# PowerSheet.net
KiCad netlist of a schematic drawn in Altium Designer
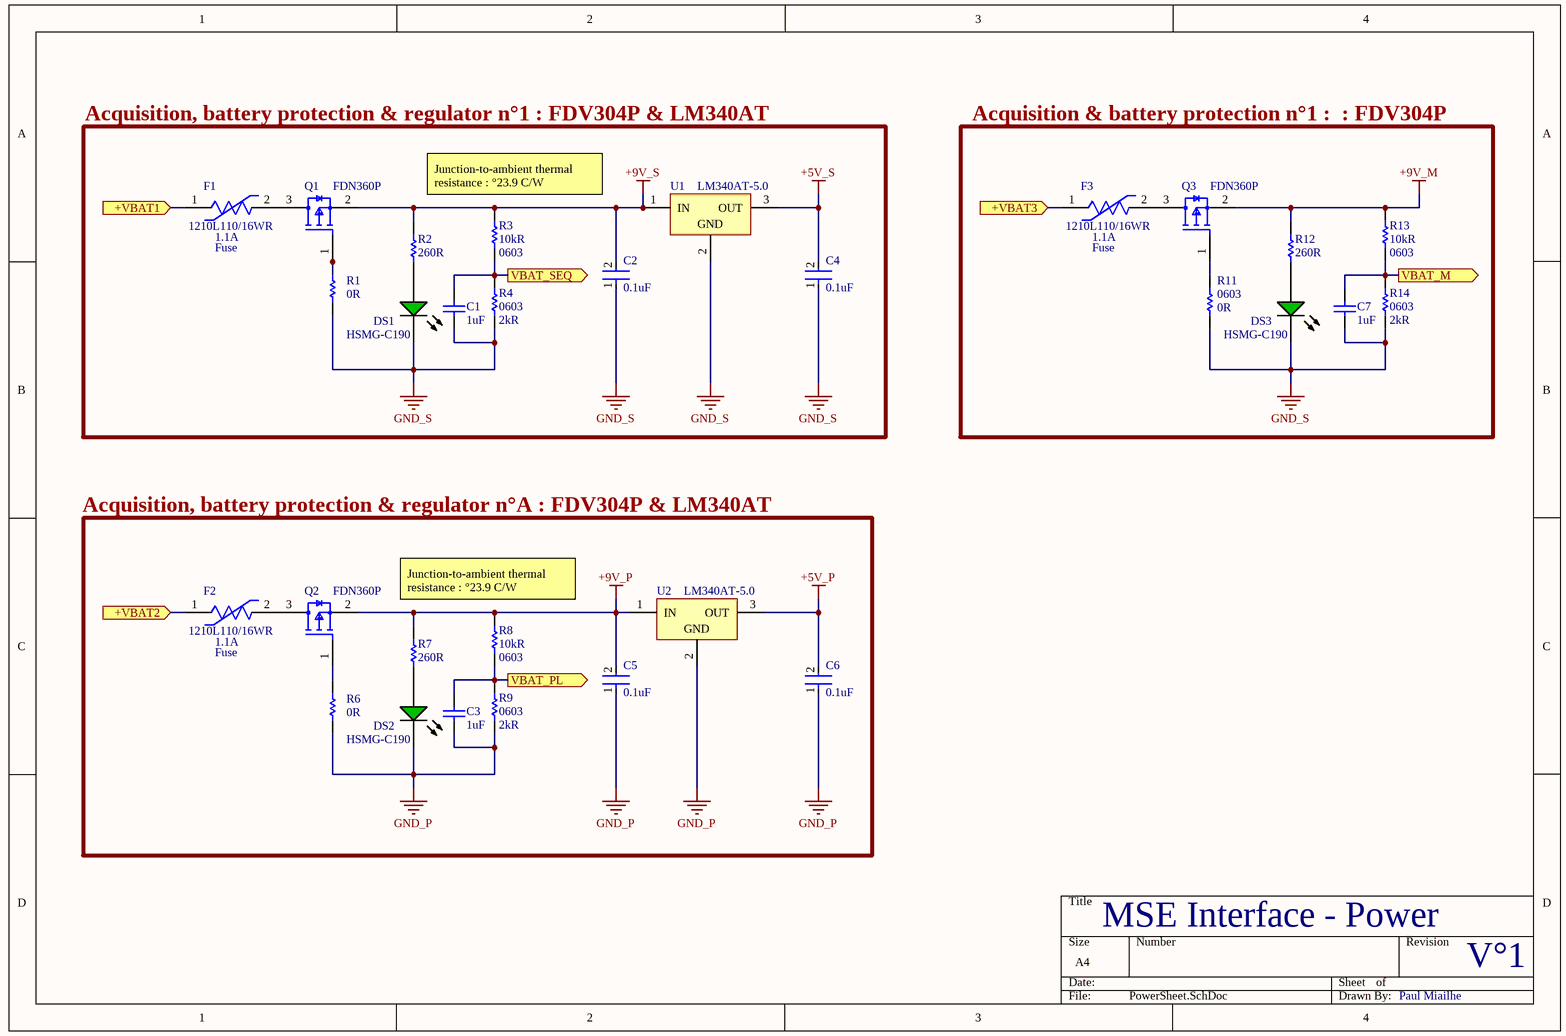
[diagram p0: PowerSheet.SchDoc]

(export (version "E")
  (design (tool "Eeschema 10.0.6"))
  (components
    (comp (ref "C1")
      (value "GRM188R61E105KA12D")
      (footprint "CAPC1608X90X35LL10T15")
      (fields
        (field (name "MANUFACTURER") "Murata")
        (field (name "CAPACITANCE") "1uF")
        (field (name "TOLERANCE") "10%")
        (field (name "VOLTAGE") "25V")
      )
      (libsource (lib "Altium Content Vault") (part "CAP"))
    )
    (comp (ref "C2")
      (value "0.1uF")
      (footprint "FP-RCE1K1-2_5-MFG")
      (description "Cap Ceramic Monolithic 220nF 50V 10% Thru-Hole Bulk")
      (fields (field (name "TOLERANCE") "10%"))
      (libsource (lib "Altium Content Vault") (part "02cd4be3c70576c341d710602a673aa"))
    )
    (comp (ref "C3")
      (value "GRM188R61E105KA12D")
      (footprint "CAPC1608X90X35LL10T15")
      (fields
        (field (name "MANUFACTURER") "Murata")
        (field (name "CAPACITANCE") "1uF")
        (field (name "TOLERANCE") "10%")
        (field (name "VOLTAGE") "25V")
      )
      (libsource (lib "Altium Content Vault") (part "CAP"))
    )
    (comp (ref "C4")
      (value "0.1uF")
      (footprint "FP-RCE1K1-2_5-MFG")
      (description "Cap Ceramic Monolithic 220nF 50V 10% Thru-Hole Bulk")
      (fields (field (name "TOLERANCE") "10%"))
      (libsource (lib "Altium Content Vault") (part "02cd4be3c70576c341d710602a673aa"))
    )
    (comp (ref "C5")
      (value "0.1uF")
      (footprint "FP-RCE1K1-2_5-MFG")
      (description "Cap Ceramic Monolithic 220nF 50V 10% Thru-Hole Bulk")
      (fields (field (name "TOLERANCE") "10%"))
      (libsource (lib "Altium Content Vault") (part "02cd4be3c70576c341d710602a673aa"))
    )
    (comp (ref "C6")
      (value "0.1uF")
      (footprint "FP-RCE1K1-2_5-MFG")
      (description "Cap Ceramic Monolithic 220nF 50V 10% Thru-Hole Bulk")
      (fields (field (name "TOLERANCE") "10%"))
      (libsource (lib "Altium Content Vault") (part "02cd4be3c70576c341d710602a673aa"))
    )
    (comp (ref "C7")
      (value "GRM188R61E105KA12D")
      (footprint "CAPC1608X90X35LL10T15")
      (fields
        (field (name "MANUFACTURER") "Murata")
        (field (name "CAPACITANCE") "1uF")
        (field (name "TOLERANCE") "10%")
        (field (name "VOLTAGE") "25V")
      )
      (libsource (lib "Altium Content Vault") (part "CAP"))
    )
    (comp (ref "DS1")
      (value "HSMG-C190")
      (footprint "AVAG-HSMX-C190_V")
      (description "Chip LED, Green, 2.2 V, -40 to 85 degC, 2-Pin SMD, RoHS, Tape and Reel")
      (libsource (lib "Altium Content Vault") (part "LED-GREEN-AK-2"))
    )
    (comp (ref "DS2")
      (value "HSMG-C190")
      (footprint "AVAG-HSMX-C190_V")
      (description "Chip LED, Green, 2.2 V, -40 to 85 degC, 2-Pin SMD, RoHS, Tape and Reel")
      (libsource (lib "Altium Content Vault") (part "LED-GREEN-AK-2"))
    )
    (comp (ref "DS3")
      (value "HSMG-C190")
      (footprint "AVAG-HSMX-C190_V")
      (description "Chip LED, Green, 2.2 V, -40 to 85 degC, 2-Pin SMD, RoHS, Tape and Reel")
      (libsource (lib "Altium Content Vault") (part "LED-GREEN-AK-2"))
    )
    (comp (ref "F1")
      (value "1210L110/16WR")
      (footprint "FP-1210L110-16WR-MFG")
      (description "PTC RESET FUSE 16V 1.1A 1210")
      (fields
        (field (name "HOLD CURRENT") "1.1A")
        (field (name "CATEGORY") "Fuse")
        (field (name "OCTOPART") "https://octopart.com/1210l110%2F16wr-littelfuse-28867107")
        (field (name "MANUFACTURER") "Littelfuse Inc")
      )
      (libsource (lib "Altium Content Vault") (part "1c6d77a0208143737455a0c7eb396be"))
    )
    (comp (ref "F2")
      (value "1210L110/16WR")
      (footprint "FP-1210L110-16WR-MFG")
      (description "PTC RESET FUSE 16V 1.1A 1210")
      (fields
        (field (name "HOLD CURRENT") "1.1A")
        (field (name "CATEGORY") "Fuse")
        (field (name "OCTOPART") "https://octopart.com/1210l110%2F16wr-littelfuse-28867107")
        (field (name "MANUFACTURER") "Littelfuse Inc")
      )
      (libsource (lib "Altium Content Vault") (part "1c6d77a0208143737455a0c7eb396be"))
    )
    (comp (ref "F3")
      (value "1210L110/16WR")
      (footprint "FP-1210L110-16WR-MFG")
      (description "PTC RESET FUSE 16V 1.1A 1210")
      (fields
        (field (name "HOLD CURRENT") "1.1A")
        (field (name "CATEGORY") "Fuse")
        (field (name "OCTOPART") "https://octopart.com/1210l110%2F16wr-littelfuse-28867107")
        (field (name "MANUFACTURER") "Littelfuse Inc")
      )
      (libsource (lib "Altium Content Vault") (part "1c6d77a0208143737455a0c7eb396be"))
    )
    (comp (ref "Q1")
      (value "FDN360P")
      (footprint "FP-527AG-IPC_B")
      (description "MOSFET P-CH 30V 2A SSOT3")
      (libsource (lib "Altium Content Vault") (part "d96140c8e79ef71348df71fb49a9466"))
    )
    (comp (ref "Q2")
      (value "FDN360P")
      (footprint "FP-527AG-IPC_B")
      (description "MOSFET P-CH 30V 2A SSOT3")
      (libsource (lib "Altium Content Vault") (part "d96140c8e79ef71348df71fb49a9466"))
    )
    (comp (ref "Q3")
      (value "FDN360P")
      (footprint "FP-527AG-IPC_B")
      (description "MOSFET P-CH 30V 2A SSOT3")
      (libsource (lib "Altium Content Vault") (part "d96140c8e79ef71348df71fb49a9466"))
    )
    (comp (ref "R1")
      (value "RC0603JR-070RL")
      (footprint "RESC1608X55X25ML10T15")
      (description "Chip Resistor, 0 Ohm, +/- 5%, 0.1 W, -55 to 155 degC, 0603 (1608 Metric), RoHS, Tape and Reel")
      (fields
        (field (name "TOLERANCE") "5%")
        (field (name "RESISTANCE") "0R")
        (field (name "MANUFACTURER") "Yageo")
      )
      (libsource (lib "Altium Content Vault") (part "RES-2"))
    )
    (comp (ref "R2")
      (value "260R")
      (footprint "RESC1609X50X30NL8T20")
      (fields (field (name "MANUFACTURER") "Vishay Semiconductor"))
      (libsource (lib "Altium Content Vault") (part "RES-2"))
    )
    (comp (ref "R3")
      (value "ERJ3EKF1002V")
      (footprint "RESC1609X55X30LL15T15")
      (description "Chip Resistor, 10 KOhm, +/- 1%, 0.1 W, -55 to 155 degC, 0603 (1608 Metric), RoHS, Tape and Reel")
      (fields
        (field (name "RESISTANCE") "10kR")
        (field (name "CASE CODE (IMPERIAL)") "0603")
        (field (name "TOLERANCE") "1%")
        (field (name "MANUFACTURER") "Panasonic")
      )
      (libsource (lib "Altium Content Vault") (part "RES-2"))
    )
    (comp (ref "R4")
      (value "ERJ-3EKF2001V")
      (footprint "RESC1608X55X30ML15T15")
      (fields
        (field (name "MANUFACTURER") "Panasonic")
        (field (name "CASE CODE (IMPERIAL)") "0603")
        (field (name "RESISTANCE") "2kR")
        (field (name "TOLERANCE") "1%")
      )
      (libsource (lib "Altium Content Vault") (part "RES"))
    )
    (comp (ref "R6")
      (value "RC0603JR-070RL")
      (footprint "RESC1608X55X25ML10T15")
      (description "Chip Resistor, 0 Ohm, +/- 5%, 0.1 W, -55 to 155 degC, 0603 (1608 Metric), RoHS, Tape and Reel")
      (fields
        (field (name "TOLERANCE") "5%")
        (field (name "RESISTANCE") "0R")
        (field (name "MANUFACTURER") "Yageo")
      )
      (libsource (lib "Altium Content Vault") (part "RES-2"))
    )
    (comp (ref "R7")
      (value "260R")
      (footprint "RESC1609X50X30NL8T20")
      (fields (field (name "MANUFACTURER") "Vishay Semiconductor"))
      (libsource (lib "Altium Content Vault") (part "RES-2"))
    )
    (comp (ref "R8")
      (value "ERJ3EKF1002V")
      (footprint "RESC1609X55X30LL15T15")
      (description "Chip Resistor, 10 KOhm, +/- 1%, 0.1 W, -55 to 155 degC, 0603 (1608 Metric), RoHS, Tape and Reel")
      (fields
        (field (name "RESISTANCE") "10kR")
        (field (name "CASE CODE (IMPERIAL)") "0603")
        (field (name "TOLERANCE") "1%")
        (field (name "MANUFACTURER") "Panasonic")
      )
      (libsource (lib "Altium Content Vault") (part "RES-2"))
    )
    (comp (ref "R9")
      (value "ERJ-3EKF2001V")
      (footprint "RESC1608X55X30ML15T15")
      (fields
        (field (name "MANUFACTURER") "Panasonic")
        (field (name "CASE CODE (IMPERIAL)") "0603")
        (field (name "RESISTANCE") "2kR")
        (field (name "TOLERANCE") "1%")
      )
      (libsource (lib "Altium Content Vault") (part "RES"))
    )
    (comp (ref "R11")
      (value "RC0603JR-070RL")
      (footprint "RESC1608X55X25ML10T15")
      (description "Chip Resistor, 0 Ohm, +/- 5%, 0.1 W, -55 to 155 degC, 0603 (1608 Metric), RoHS, Tape and Reel")
      (fields
        (field (name "TOLERANCE") "5%")
        (field (name "PACKAGE REFERENCE") "0603")
        (field (name "RESISTANCE") "0R")
        (field (name "MANUFACTURER") "Yageo")
      )
      (libsource (lib "Altium Content Vault") (part "RES-2"))
    )
    (comp (ref "R12")
      (value "260R")
      (footprint "RESC1609X50X30NL8T20")
      (fields (field (name "MANUFACTURER") "Vishay Semiconductor"))
      (libsource (lib "Altium Content Vault") (part "RES-2"))
    )
    (comp (ref "R13")
      (value "ERJ3EKF1002V")
      (footprint "RESC1609X55X30LL15T15")
      (description "Chip Resistor, 10 KOhm, +/- 1%, 0.1 W, -55 to 155 degC, 0603 (1608 Metric), RoHS, Tape and Reel")
      (fields
        (field (name "RESISTANCE") "10kR")
        (field (name "CASE CODE (IMPERIAL)") "0603")
        (field (name "TOLERANCE") "1%")
        (field (name "MANUFACTURER") "Panasonic")
      )
      (libsource (lib "Altium Content Vault") (part "RES-2"))
    )
    (comp (ref "R14")
      (value "ERJ-3EKF2001V")
      (footprint "RESC1608X55X30ML15T15")
      (fields
        (field (name "MANUFACTURER") "Panasonic")
        (field (name "CASE CODE (IMPERIAL)") "0603")
        (field (name "RESISTANCE") "2kR")
        (field (name "TOLERANCE") "1%")
      )
      (libsource (lib "Altium Content Vault") (part "RES"))
    )
    (comp (ref "U1")
      (value "LM340AT-5.0")
      (footprint "NDE0003A")
      (description "Series 3-Terminal Positive Regulators, 3-pin TO-220")
      (fields (field (name "MANUFACTURER") "Texas Instruments"))
      (libsource (lib "Altium Content Vault") (part "PM-REG-LM2940-SIL3"))
    )
    (comp (ref "U2")
      (value "LM340AT-5.0")
      (footprint "NDE0003A")
      (description "Series 3-Terminal Positive Regulators, 3-pin TO-220")
      (fields (field (name "MANUFACTURER") "Texas Instruments"))
      (libsource (lib "Altium Content Vault") (part "PM-REG-LM2940-SIL3"))
    )
  )
  (nets
    (net (code "1") (name "+5V_P") (class "Default")
      (node (ref "C6") (pin "2") (pinfunction "2_2") (pintype "passive"))
      (node (ref "U2") (pin "3") (pinfunction "OUT_3") (pintype "power_in"))
    )
    (net (code "2") (name "+5V_S") (class "Default")
      (node (ref "C4") (pin "2") (pinfunction "2_2") (pintype "passive"))
      (node (ref "U1") (pin "3") (pinfunction "OUT_3") (pintype "power_in"))
    )
    (net (code "3") (name "+9V_M") (class "Default")
      (node (ref "Q3") (pin "2") (pinfunction "S_2") (pintype "passive"))
      (node (ref "R12") (pin "1") (pinfunction "1_1") (pintype "passive"))
      (node (ref "R13") (pin "2") (pinfunction "2_2") (pintype "passive"))
    )
    (net (code "4") (name "+9V_P") (class "Default")
      (node (ref "C5") (pin "2") (pinfunction "2_2") (pintype "passive"))
      (node (ref "Q2") (pin "2") (pinfunction "S_2") (pintype "passive"))
      (node (ref "R7") (pin "1") (pinfunction "1_1") (pintype "passive"))
      (node (ref "R8") (pin "2") (pinfunction "2_2") (pintype "passive"))
      (node (ref "U2") (pin "1") (pinfunction "IN_1") (pintype "power_in"))
    )
    (net (code "5") (name "+9V_S") (class "Default")
      (node (ref "C2") (pin "2") (pinfunction "2_2") (pintype "passive"))
      (node (ref "Q1") (pin "2") (pinfunction "S_2") (pintype "passive"))
      (node (ref "R2") (pin "1") (pinfunction "1_1") (pintype "passive"))
      (node (ref "R3") (pin "2") (pinfunction "2_2") (pintype "passive"))
      (node (ref "U1") (pin "1") (pinfunction "IN_1") (pintype "power_in"))
    )
    (net (code "6") (name "/+VBAT1") (class "Default")
      (node (ref "F1") (pin "1") (pinfunction "1_1") (pintype "passive"))
    )
    (net (code "7") (name "/+VBAT2") (class "Default")
      (node (ref "F2") (pin "1") (pinfunction "1_1") (pintype "passive"))
    )
    (net (code "8") (name "/+VBAT3") (class "Default")
      (node (ref "F3") (pin "1") (pinfunction "1_1") (pintype "passive"))
    )
    (net (code "9") (name "/VBAT_M") (class "Default")
      (node (ref "C7") (pin "2") (pinfunction "2_2") (pintype "passive"))
      (node (ref "R13") (pin "1") (pinfunction "1_1") (pintype "passive"))
      (node (ref "R14") (pin "2") (pinfunction "2_2") (pintype "passive"))
    )
    (net (code "10") (name "/VBAT_PL") (class "Default")
      (node (ref "C3") (pin "2") (pinfunction "2_2") (pintype "passive"))
      (node (ref "R8") (pin "1") (pinfunction "1_1") (pintype "passive"))
      (node (ref "R9") (pin "2") (pinfunction "2_2") (pintype "passive"))
    )
    (net (code "11") (name "/VBAT_SEQ") (class "Default")
      (node (ref "C1") (pin "2") (pinfunction "2_2") (pintype "passive"))
      (node (ref "R3") (pin "1") (pinfunction "1_1") (pintype "passive"))
      (node (ref "R4") (pin "2") (pinfunction "2_2") (pintype "passive"))
    )
    (net (code "12") (name "GND_P") (class "Default")
      (node (ref "C3") (pin "1") (pinfunction "1_1") (pintype "passive"))
      (node (ref "C5") (pin "1") (pinfunction "1_1") (pintype "passive"))
      (node (ref "C6") (pin "1") (pinfunction "1_1") (pintype "passive"))
      (node (ref "DS2") (pin "2") (pinfunction "K_2") (pintype "passive"))
      (node (ref "R6") (pin "1") (pinfunction "1_1") (pintype "passive"))
      (node (ref "R9") (pin "1") (pinfunction "1_1") (pintype "passive"))
      (node (ref "U2") (pin "2") (pinfunction "GND_2") (pintype "power_in"))
    )
    (net (code "13") (name "GND_S") (class "Default")
      (node (ref "C1") (pin "1") (pinfunction "1_1") (pintype "passive"))
      (node (ref "C2") (pin "1") (pinfunction "1_1") (pintype "passive"))
      (node (ref "C4") (pin "1") (pinfunction "1_1") (pintype "passive"))
      (node (ref "C7") (pin "1") (pinfunction "1_1") (pintype "passive"))
      (node (ref "DS1") (pin "2") (pinfunction "K_2") (pintype "passive"))
      (node (ref "DS3") (pin "2") (pinfunction "K_2") (pintype "passive"))
      (node (ref "R1") (pin "1") (pinfunction "1_1") (pintype "passive"))
      (node (ref "R11") (pin "1") (pinfunction "1_1") (pintype "passive"))
      (node (ref "R14") (pin "1") (pinfunction "1_1") (pintype "passive"))
      (node (ref "R4") (pin "1") (pinfunction "1_1") (pintype "passive"))
      (node (ref "U1") (pin "2") (pinfunction "GND_2") (pintype "power_in"))
    )
    (net (code "14") (name "Net-(DS1-A)") (class "Default")
      (node (ref "DS1") (pin "1") (pinfunction "A_1") (pintype "passive"))
      (node (ref "R2") (pin "2") (pinfunction "2_2") (pintype "passive"))
    )
    (net (code "15") (name "Net-(DS2-A)") (class "Default")
      (node (ref "DS2") (pin "1") (pinfunction "A_1") (pintype "passive"))
      (node (ref "R7") (pin "2") (pinfunction "2_2") (pintype "passive"))
    )
    (net (code "16") (name "Net-(DS3-A)") (class "Default")
      (node (ref "DS3") (pin "1") (pinfunction "A_1") (pintype "passive"))
      (node (ref "R12") (pin "2") (pinfunction "2_2") (pintype "passive"))
    )
    (net (code "17") (name "Net-(Q1-D)") (class "Default")
      (node (ref "F1") (pin "2") (pinfunction "2_2") (pintype "passive"))
      (node (ref "Q1") (pin "3") (pinfunction "D_3") (pintype "passive"))
    )
    (net (code "18") (name "Net-(Q1-G)") (class "Default")
      (node (ref "Q1") (pin "1") (pinfunction "G_1") (pintype "passive"))
      (node (ref "R1") (pin "2") (pinfunction "2_2") (pintype "passive"))
    )
    (net (code "19") (name "Net-(Q2-D)") (class "Default")
      (node (ref "F2") (pin "2") (pinfunction "2_2") (pintype "passive"))
      (node (ref "Q2") (pin "3") (pinfunction "D_3") (pintype "passive"))
    )
    (net (code "20") (name "Net-(Q2-G)") (class "Default")
      (node (ref "Q2") (pin "1") (pinfunction "G_1") (pintype "passive"))
      (node (ref "R6") (pin "2") (pinfunction "2_2") (pintype "passive"))
    )
    (net (code "21") (name "Net-(Q3-D)") (class "Default")
      (node (ref "F3") (pin "2") (pinfunction "2_2") (pintype "passive"))
      (node (ref "Q3") (pin "3") (pinfunction "D_3") (pintype "passive"))
    )
    (net (code "22") (name "Net-(Q3-G)") (class "Default")
      (node (ref "Q3") (pin "1") (pinfunction "G_1") (pintype "passive"))
      (node (ref "R11") (pin "2") (pinfunction "2_2") (pintype "passive"))
    )
  )
)
